# IMUOld.net
KiCad netlist of a schematic drawn in Altium Designer
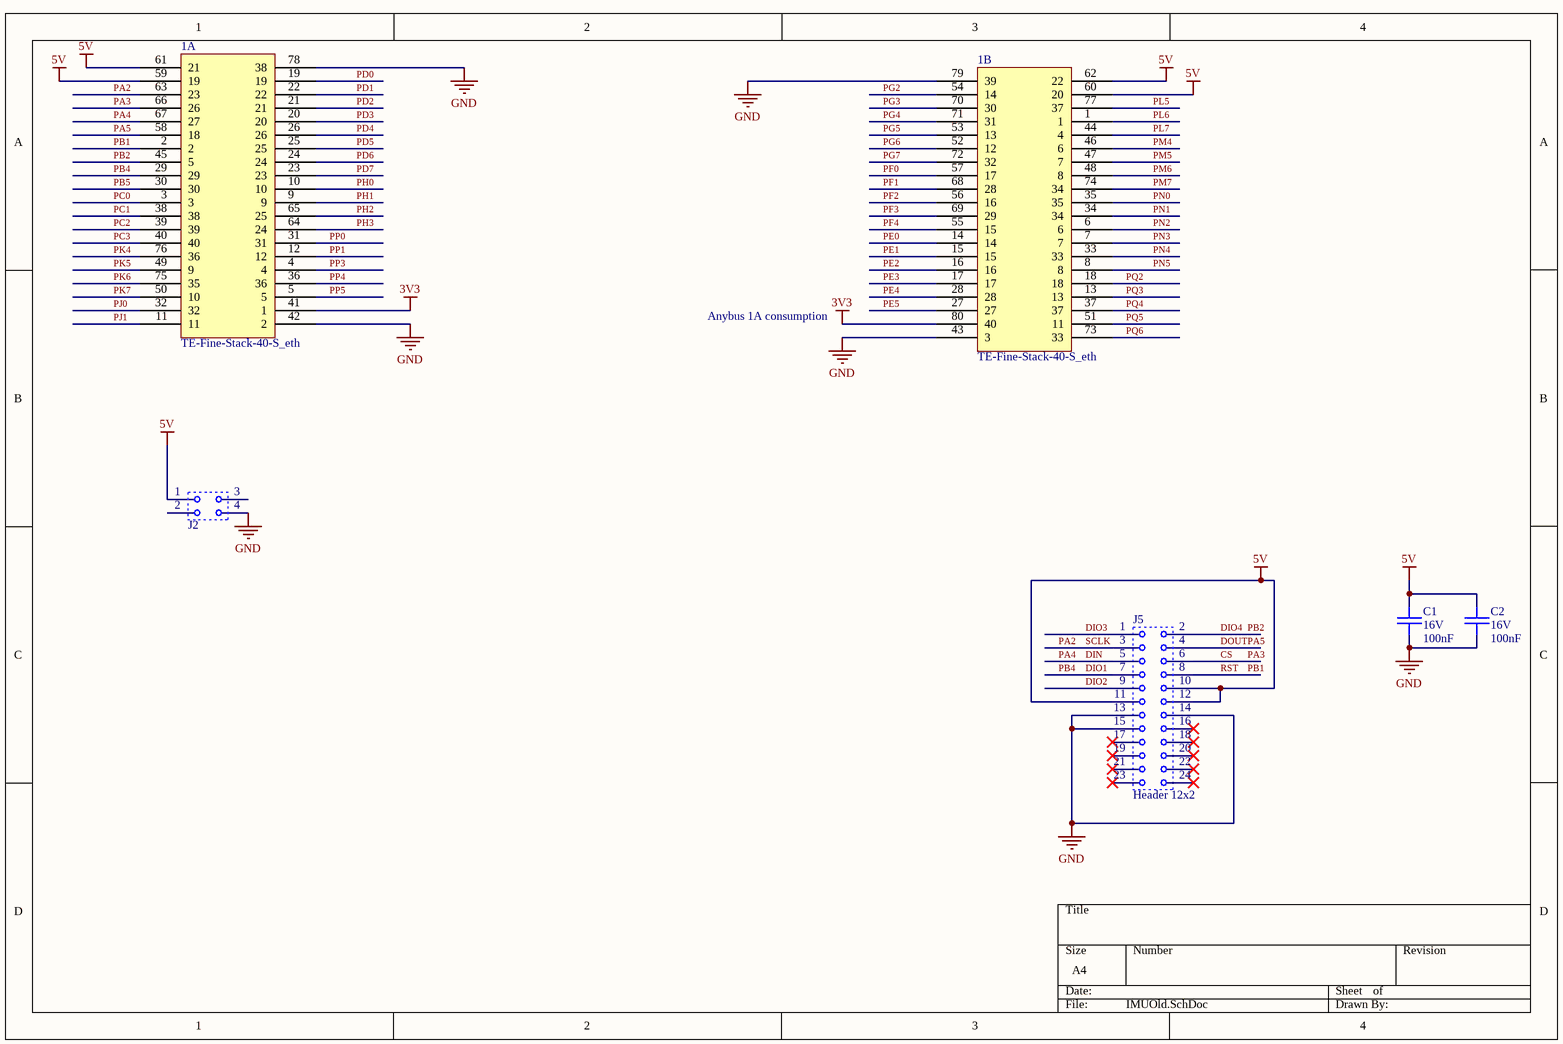
[diagram p0: IMUOld.SchDoc]

(export (version "E")
  (design (tool "Eeschema 10.0.6"))
  (components
    (comp (ref "1")
      (value "TE-Fine-Stack-40-S_eth")
      (footprint "TE-FINE-STACK-40-P-Eth")
      (libsource (lib "Connectors") (part "TE-Fine-Stack-40-S_eth"))
    )
    (comp (ref "C1")
      (value "100nF")
      (footprint "Other-Discrete:0805")
      (description "Ceramic Capacitor")
      (fields (field (name "VOLTAGE") "16V") (field (name "Comment") "100n"))
      (libsource (lib "Disc-Other") (part "C_CER"))
    )
    (comp (ref "C2")
      (value "100nF")
      (footprint "Other-Discrete:0805")
      (description "Ceramic Capacitor")
      (fields (field (name "VOLTAGE") "16V") (field (name "Comment") "100n"))
      (libsource (lib "Disc-Other") (part "C_CER"))
    )
    (comp (ref "J2")
      (value "Molex Microfit")
      (footprint "MicroFit:MICROFIT 2x2 Right Angle")
      (libsource (lib "Connectors") (part "Microfit 2x2 Right Angle"))
    )
    (comp (ref "J5")
      (value "Header 12x2")
      (footprint "CLM-112-02")
      (libsource (lib "Connectors") (part "Header 12x2"))
    )
  )
  (nets
    (net (code "1") (name "/CS") (class "Default")
      (node (ref "1") (pin "66") (pinfunction "26_66") (pintype "passive"))
      (node (ref "J5") (pin "6") (pintype "passive"))
    )
    (net (code "2") (name "/DIN") (class "Default")
      (node (ref "1") (pin "67") (pinfunction "27_67") (pintype "passive"))
      (node (ref "J5") (pin "5") (pintype "passive"))
    )
    (net (code "3") (name "/DIO1") (class "Default")
      (node (ref "1") (pin "29") (pinfunction "29_29") (pintype "passive"))
      (node (ref "J5") (pin "7") (pintype "passive"))
    )
    (net (code "4") (name "/DIO2") (class "Default") (node (ref "J5") (pin "9") (pintype "passive")))
    (net (code "5") (name "/DIO3") (class "Default") (node (ref "J5") (pin "1") (pintype "passive")))
    (net (code "6") (name "/DIO4") (class "Default")
      (node (ref "1") (pin "45") (pinfunction "5_45") (pintype "passive"))
      (node (ref "J5") (pin "2") (pintype "passive"))
    )
    (net (code "7") (name "/DOUT") (class "Default")
      (node (ref "1") (pin "58") (pinfunction "18_58") (pintype "passive"))
      (node (ref "J5") (pin "4") (pintype "passive"))
    )
    (net (code "8") (name "/PA2") (class "Default")
      (node (ref "1") (pin "63") (pinfunction "23_63") (pintype "passive"))
      (node (ref "J5") (pin "3") (pintype "passive"))
    )
    (net (code "9") (name "/PB1") (class "Default")
      (node (ref "1") (pin "2") (pinfunction "2_2") (pintype "passive"))
      (node (ref "J5") (pin "8") (pintype "passive"))
    )
    (net (code "10") (name "/PB5") (class "Default")
      (node (ref "1") (pin "30") (pinfunction "30_30") (pintype "passive"))
    )
    (net (code "11") (name "/PC0") (class "Default")
      (node (ref "1") (pin "3") (pinfunction "3_3") (pintype "passive"))
    )
    (net (code "12") (name "/PC1") (class "Default")
      (node (ref "1") (pin "38") (pinfunction "38_38") (pintype "passive"))
    )
    (net (code "13") (name "/PC2") (class "Default")
      (node (ref "1") (pin "39") (pinfunction "39_39") (pintype "passive"))
    )
    (net (code "14") (name "/PC3") (class "Default")
      (node (ref "1") (pin "40") (pinfunction "40_40") (pintype "passive"))
    )
    (net (code "15") (name "/PD0") (class "Default")
      (node (ref "1") (pin "19") (pinfunction "19_19") (pintype "passive"))
    )
    (net (code "16") (name "/PD1") (class "Default")
      (node (ref "1") (pin "22") (pinfunction "22_22") (pintype "passive"))
    )
    (net (code "17") (name "/PD2") (class "Default")
      (node (ref "1") (pin "21") (pinfunction "21_21") (pintype "passive"))
    )
    (net (code "18") (name "/PD3") (class "Default")
      (node (ref "1") (pin "20") (pinfunction "20_20") (pintype "passive"))
    )
    (net (code "19") (name "/PD4") (class "Default")
      (node (ref "1") (pin "26") (pinfunction "26_26") (pintype "passive"))
    )
    (net (code "20") (name "/PD5") (class "Default")
      (node (ref "1") (pin "25") (pinfunction "25_25") (pintype "passive"))
    )
    (net (code "21") (name "/PD6") (class "Default")
      (node (ref "1") (pin "24") (pinfunction "24_24") (pintype "passive"))
    )
    (net (code "22") (name "/PD7") (class "Default")
      (node (ref "1") (pin "23") (pinfunction "23_23") (pintype "passive"))
    )
    (net (code "23") (name "/PE0") (class "Default")
      (node (ref "1") (pin "14") (pinfunction "14_14") (pintype "passive"))
    )
    (net (code "24") (name "/PE1") (class "Default")
      (node (ref "1") (pin "15") (pinfunction "15_15") (pintype "passive"))
    )
    (net (code "25") (name "/PE2") (class "Default")
      (node (ref "1") (pin "16") (pinfunction "16_16") (pintype "passive"))
    )
    (net (code "26") (name "/PE3") (class "Default")
      (node (ref "1") (pin "17") (pinfunction "17_17") (pintype "passive"))
    )
    (net (code "27") (name "/PE4") (class "Default")
      (node (ref "1") (pin "28") (pinfunction "28_28") (pintype "passive"))
    )
    (net (code "28") (name "/PE5") (class "Default")
      (node (ref "1") (pin "27") (pinfunction "27_27") (pintype "passive"))
    )
    (net (code "29") (name "/PF0") (class "Default")
      (node (ref "1") (pin "57") (pinfunction "17_57") (pintype "passive"))
    )
    (net (code "30") (name "/PF1") (class "Default")
      (node (ref "1") (pin "68") (pinfunction "28_68") (pintype "passive"))
    )
    (net (code "31") (name "/PF2") (class "Default")
      (node (ref "1") (pin "56") (pinfunction "16_56") (pintype "passive"))
    )
    (net (code "32") (name "/PF3") (class "Default")
      (node (ref "1") (pin "69") (pinfunction "29_69") (pintype "passive"))
    )
    (net (code "33") (name "/PF4") (class "Default")
      (node (ref "1") (pin "55") (pinfunction "15_55") (pintype "passive"))
    )
    (net (code "34") (name "/PG2") (class "Default")
      (node (ref "1") (pin "54") (pinfunction "14_54") (pintype "passive"))
    )
    (net (code "35") (name "/PG3") (class "Default")
      (node (ref "1") (pin "70") (pinfunction "30_70") (pintype "passive"))
    )
    (net (code "36") (name "/PG4") (class "Default")
      (node (ref "1") (pin "71") (pinfunction "31_71") (pintype "passive"))
    )
    (net (code "37") (name "/PG5") (class "Default")
      (node (ref "1") (pin "53") (pinfunction "13_53") (pintype "passive"))
    )
    (net (code "38") (name "/PG6") (class "Default")
      (node (ref "1") (pin "52") (pinfunction "12_52") (pintype "passive"))
    )
    (net (code "39") (name "/PG7") (class "Default")
      (node (ref "1") (pin "72") (pinfunction "32_72") (pintype "passive"))
    )
    (net (code "40") (name "/PH0") (class "Default")
      (node (ref "1") (pin "10") (pinfunction "10_10") (pintype "passive"))
    )
    (net (code "41") (name "/PH1") (class "Default")
      (node (ref "1") (pin "9") (pinfunction "9_9") (pintype "passive"))
    )
    (net (code "42") (name "/PH2") (class "Default")
      (node (ref "1") (pin "65") (pinfunction "25_65") (pintype "passive"))
    )
    (net (code "43") (name "/PH3") (class "Default")
      (node (ref "1") (pin "64") (pinfunction "24_64") (pintype "passive"))
    )
    (net (code "44") (name "/PJ0") (class "Default")
      (node (ref "1") (pin "32") (pinfunction "32_32") (pintype "passive"))
    )
    (net (code "45") (name "/PJ1") (class "Default")
      (node (ref "1") (pin "11") (pinfunction "11_11") (pintype "passive"))
    )
    (net (code "46") (name "/PK4") (class "Default")
      (node (ref "1") (pin "76") (pinfunction "36_76") (pintype "passive"))
    )
    (net (code "47") (name "/PK5") (class "Default")
      (node (ref "1") (pin "49") (pinfunction "9_49") (pintype "passive"))
    )
    (net (code "48") (name "/PK6") (class "Default")
      (node (ref "1") (pin "75") (pinfunction "35_75") (pintype "passive"))
    )
    (net (code "49") (name "/PK7") (class "Default")
      (node (ref "1") (pin "50") (pinfunction "10_50") (pintype "passive"))
    )
    (net (code "50") (name "/PL5") (class "Default")
      (node (ref "1") (pin "77") (pinfunction "37_77") (pintype "passive"))
    )
    (net (code "51") (name "/PL6") (class "Default")
      (node (ref "1") (pin "1") (pinfunction "1_1") (pintype "passive"))
    )
    (net (code "52") (name "/PL7") (class "Default")
      (node (ref "1") (pin "44") (pinfunction "4_44") (pintype "passive"))
    )
    (net (code "53") (name "/PM4") (class "Default")
      (node (ref "1") (pin "46") (pinfunction "6_46") (pintype "passive"))
    )
    (net (code "54") (name "/PM5") (class "Default")
      (node (ref "1") (pin "47") (pinfunction "7_47") (pintype "passive"))
    )
    (net (code "55") (name "/PM6") (class "Default")
      (node (ref "1") (pin "48") (pinfunction "8_48") (pintype "passive"))
    )
    (net (code "56") (name "/PM7") (class "Default")
      (node (ref "1") (pin "74") (pinfunction "34_74") (pintype "passive"))
    )
    (net (code "57") (name "/PN0") (class "Default")
      (node (ref "1") (pin "35") (pinfunction "35_35") (pintype "passive"))
    )
    (net (code "58") (name "/PN1") (class "Default")
      (node (ref "1") (pin "34") (pinfunction "34_34") (pintype "passive"))
    )
    (net (code "59") (name "/PN2") (class "Default")
      (node (ref "1") (pin "6") (pinfunction "6_6") (pintype "passive"))
    )
    (net (code "60") (name "/PN3") (class "Default")
      (node (ref "1") (pin "7") (pinfunction "7_7") (pintype "passive"))
    )
    (net (code "61") (name "/PN4") (class "Default")
      (node (ref "1") (pin "33") (pinfunction "33_33") (pintype "passive"))
    )
    (net (code "62") (name "/PN5") (class "Default")
      (node (ref "1") (pin "8") (pinfunction "8_8") (pintype "passive"))
    )
    (net (code "63") (name "/PP0") (class "Default")
      (node (ref "1") (pin "31") (pinfunction "31_31") (pintype "passive"))
    )
    (net (code "64") (name "/PP1") (class "Default")
      (node (ref "1") (pin "12") (pinfunction "12_12") (pintype "passive"))
    )
    (net (code "65") (name "/PP3") (class "Default")
      (node (ref "1") (pin "4") (pinfunction "4_4") (pintype "passive"))
    )
    (net (code "66") (name "/PP4") (class "Default")
      (node (ref "1") (pin "36") (pinfunction "36_36") (pintype "passive"))
    )
    (net (code "67") (name "/PP5") (class "Default")
      (node (ref "1") (pin "5") (pinfunction "5_5") (pintype "passive"))
    )
    (net (code "68") (name "/PQ2") (class "Default")
      (node (ref "1") (pin "18") (pinfunction "18_18") (pintype "passive"))
    )
    (net (code "69") (name "/PQ3") (class "Default")
      (node (ref "1") (pin "13") (pinfunction "13_13") (pintype "passive"))
    )
    (net (code "70") (name "/PQ4") (class "Default")
      (node (ref "1") (pin "37") (pinfunction "37_37") (pintype "passive"))
    )
    (net (code "71") (name "/PQ5") (class "Default")
      (node (ref "1") (pin "51") (pinfunction "11_51") (pintype "passive"))
    )
    (net (code "72") (name "/PQ6") (class "Default")
      (node (ref "1") (pin "73") (pinfunction "33_73") (pintype "passive"))
    )
    (net (code "73") (name "3V3") (class "Default")
      (node (ref "1") (pin "41") (pinfunction "1_41") (pintype "passive"))
      (node (ref "1") (pin "80") (pinfunction "40_80") (pintype "passive"))
    )
    (net (code "74") (name "5V") (class "Default")
      (node (ref "1") (pin "59") (pinfunction "19_59") (pintype "passive"))
      (node (ref "1") (pin "60") (pinfunction "20_60") (pintype "passive"))
      (node (ref "1") (pin "61") (pinfunction "21_61") (pintype "passive"))
      (node (ref "1") (pin "62") (pinfunction "22_62") (pintype "passive"))
      (node (ref "C1") (pin "1") (pinfunction "1_1") (pintype "passive"))
      (node (ref "C2") (pin "1") (pinfunction "1_1") (pintype "passive"))
      (node (ref "J2") (pin "1") (pintype "passive"))
      (node (ref "J5") (pin "10") (pintype "passive"))
      (node (ref "J5") (pin "11") (pintype "passive"))
      (node (ref "J5") (pin "12") (pintype "passive"))
    )
    (net (code "75") (name "GND") (class "Default")
      (node (ref "1") (pin "42") (pinfunction "2_42") (pintype "passive"))
      (node (ref "1") (pin "43") (pinfunction "3_43") (pintype "passive"))
      (node (ref "1") (pin "78") (pinfunction "38_78") (pintype "passive"))
      (node (ref "1") (pin "79") (pinfunction "39_79") (pintype "passive"))
      (node (ref "C1") (pin "2") (pinfunction "2_2") (pintype "passive"))
      (node (ref "C2") (pin "2") (pinfunction "2_2") (pintype "passive"))
      (node (ref "J2") (pin "4") (pintype "passive"))
      (node (ref "J5") (pin "13") (pintype "passive"))
      (node (ref "J5") (pin "14") (pintype "passive"))
      (node (ref "J5") (pin "15") (pintype "passive"))
    )
    (net (code "76") (name "unconnected-(J2-Pad2)") (class "Default")
      (node (ref "J2") (pin "2") (pintype "passive"))
    )
    (net (code "77") (name "unconnected-(J2-Pad3)") (class "Default")
      (node (ref "J2") (pin "3") (pintype "passive"))
    )
    (net (code "78") (name "unconnected-(J5-Pad16)") (class "Default")
      (node (ref "J5") (pin "16") (pintype "passive+no_connect"))
    )
    (net (code "79") (name "unconnected-(J5-Pad17)") (class "Default")
      (node (ref "J5") (pin "17") (pintype "passive+no_connect"))
    )
    (net (code "80") (name "unconnected-(J5-Pad18)") (class "Default")
      (node (ref "J5") (pin "18") (pintype "passive+no_connect"))
    )
    (net (code "81") (name "unconnected-(J5-Pad19)") (class "Default")
      (node (ref "J5") (pin "19") (pintype "passive+no_connect"))
    )
    (net (code "82") (name "unconnected-(J5-Pad20)") (class "Default")
      (node (ref "J5") (pin "20") (pintype "passive+no_connect"))
    )
    (net (code "83") (name "unconnected-(J5-Pad21)") (class "Default")
      (node (ref "J5") (pin "21") (pintype "passive+no_connect"))
    )
    (net (code "84") (name "unconnected-(J5-Pad22)") (class "Default")
      (node (ref "J5") (pin "22") (pintype "passive+no_connect"))
    )
    (net (code "85") (name "unconnected-(J5-Pad23)") (class "Default")
      (node (ref "J5") (pin "23") (pintype "passive+no_connect"))
    )
    (net (code "86") (name "unconnected-(J5-Pad24)") (class "Default")
      (node (ref "J5") (pin "24") (pintype "passive+no_connect"))
    )
  )
)
